# CRSC0002_MCU.net
KiCad netlist of a schematic drawn in Altium Designer
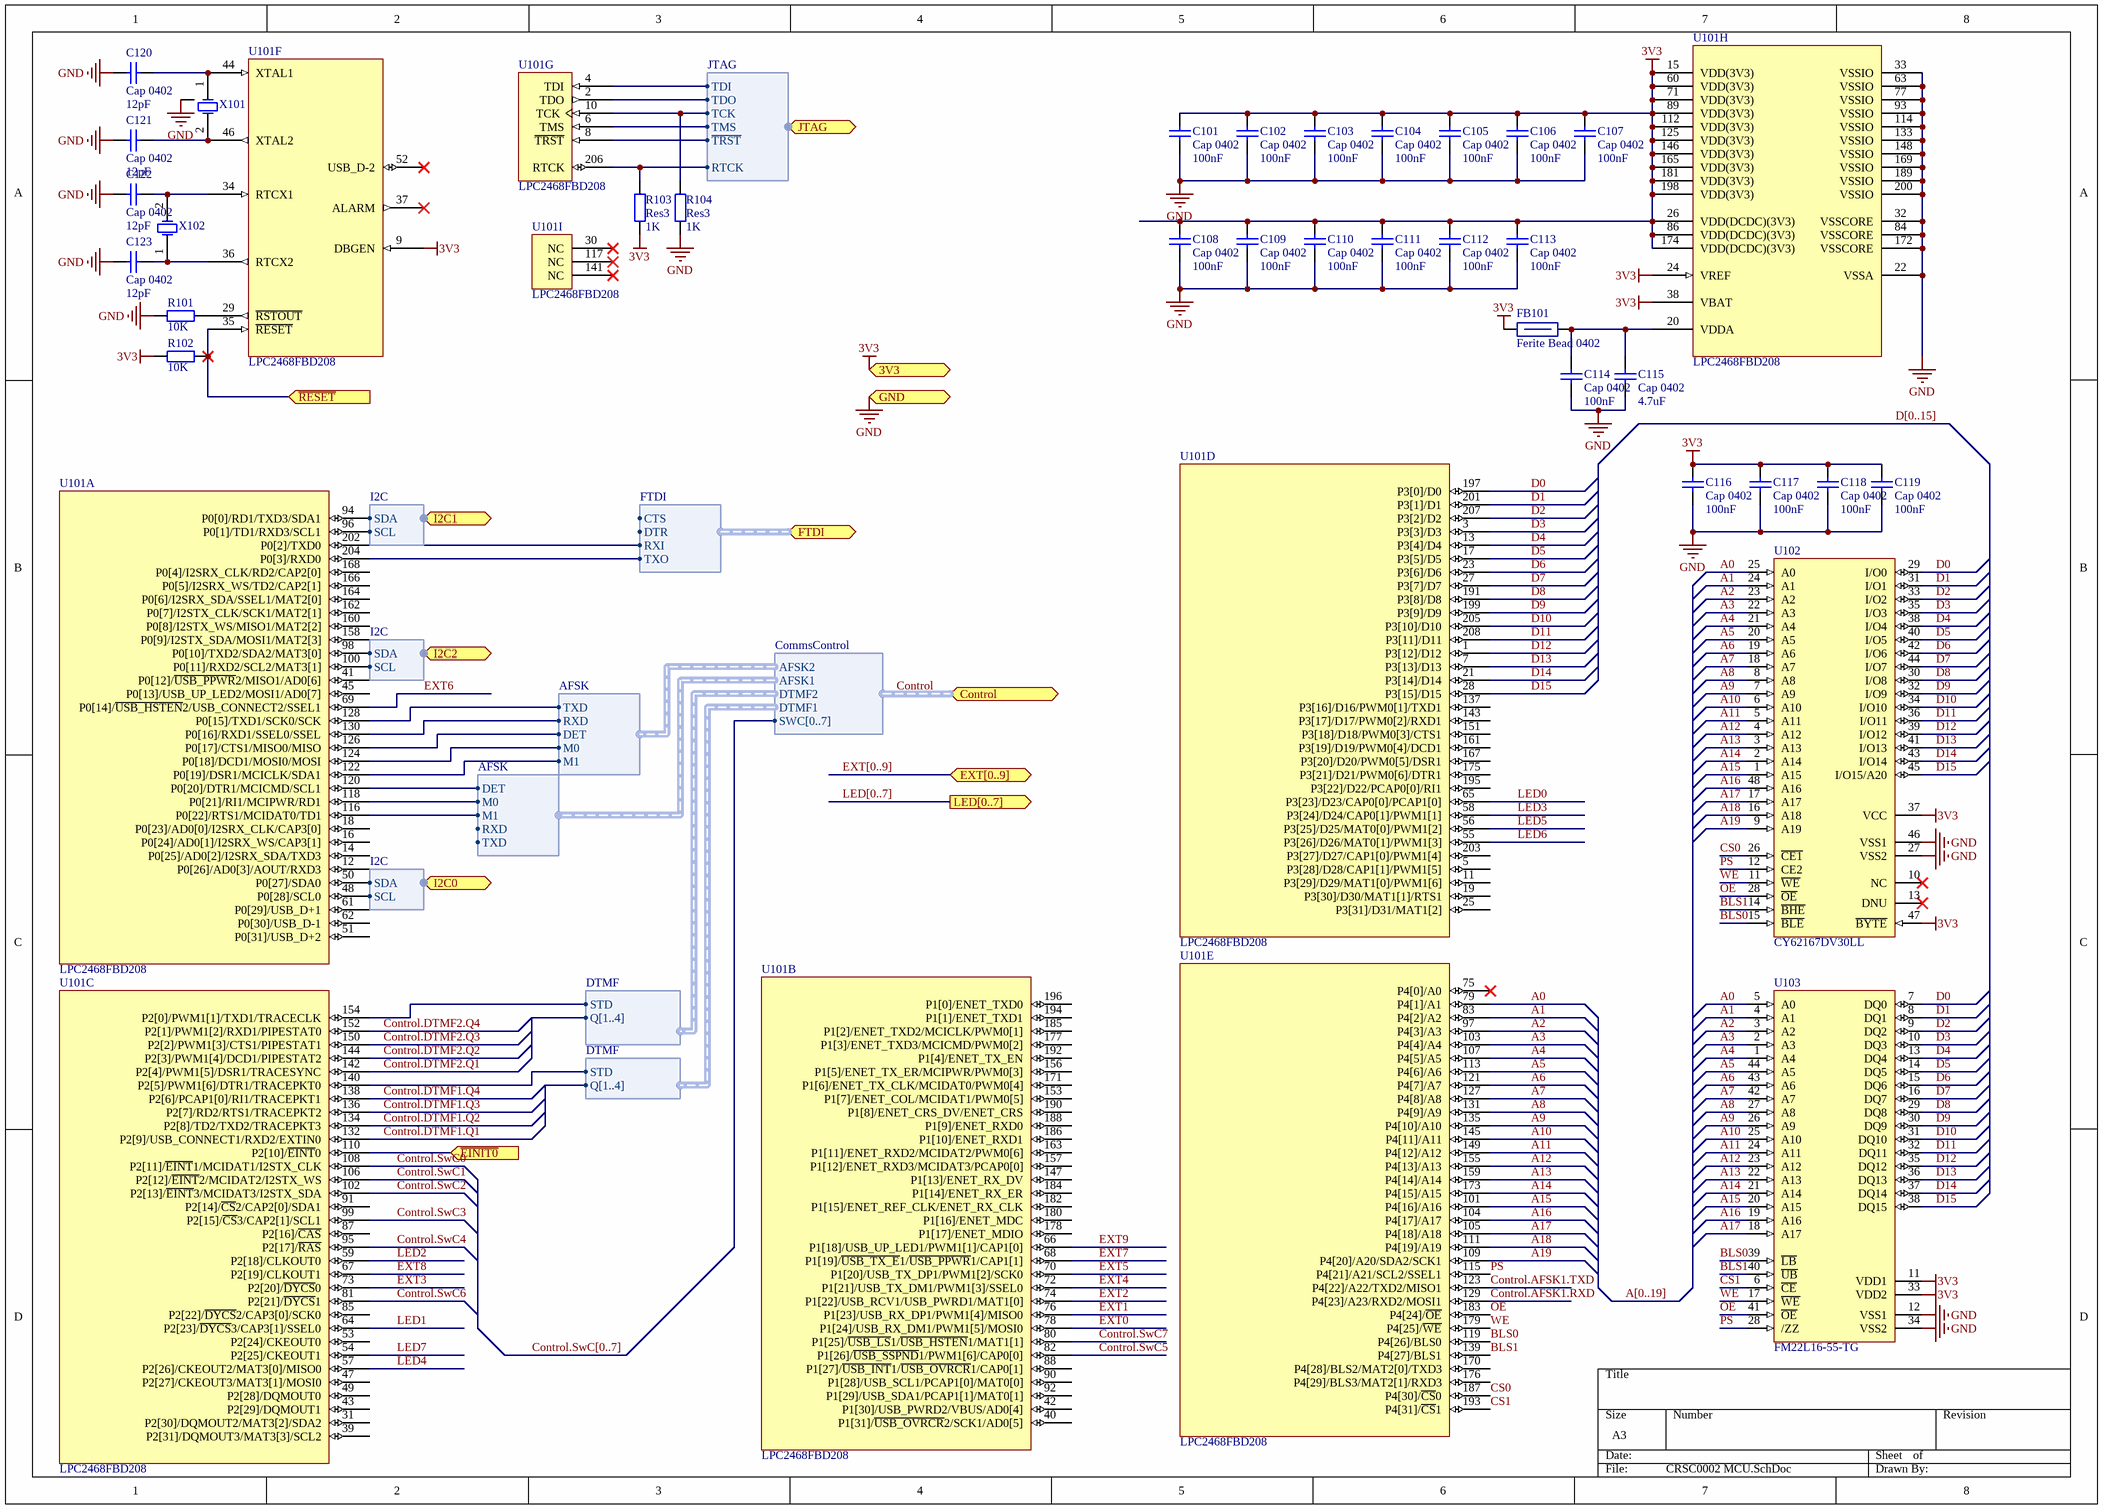
[diagram p0: CRSC0002 MCU.SchDoc]

(export (version "E")
  (design (tool "Eeschema 10.0.6"))
  (components
    (comp (ref "C101")
      (value "Cap 0402")
      (footprint "CAPC1005X06L")
      (description "Capacitor")
      (fields (field (name "ALTIUM_VALUE") "100nF") (field (name "PUBLISHER") "Altium Limited"))
      (libsource (lib "CSC") (part "Cap 0402"))
    )
    (comp (ref "C102")
      (value "Cap 0402")
      (footprint "CAPC1005X06L")
      (description "Capacitor")
      (fields (field (name "ALTIUM_VALUE") "100nF") (field (name "PUBLISHER") "Altium Limited"))
      (libsource (lib "CSC") (part "Cap 0402"))
    )
    (comp (ref "C103")
      (value "Cap 0402")
      (footprint "CAPC1005X06L")
      (description "Capacitor")
      (fields (field (name "ALTIUM_VALUE") "100nF") (field (name "PUBLISHER") "Altium Limited"))
      (libsource (lib "CSC") (part "Cap 0402"))
    )
    (comp (ref "C104")
      (value "Cap 0402")
      (footprint "CAPC1005X06L")
      (description "Capacitor")
      (fields (field (name "ALTIUM_VALUE") "100nF") (field (name "PUBLISHER") "Altium Limited"))
      (libsource (lib "CSC") (part "Cap 0402"))
    )
    (comp (ref "C105")
      (value "Cap 0402")
      (footprint "CAPC1005X06L")
      (description "Capacitor")
      (fields (field (name "ALTIUM_VALUE") "100nF") (field (name "PUBLISHER") "Altium Limited"))
      (libsource (lib "CSC") (part "Cap 0402"))
    )
    (comp (ref "C106")
      (value "Cap 0402")
      (footprint "CAPC1005X06L")
      (description "Capacitor")
      (fields (field (name "ALTIUM_VALUE") "100nF") (field (name "PUBLISHER") "Altium Limited"))
      (libsource (lib "CSC") (part "Cap 0402"))
    )
    (comp (ref "C107")
      (value "Cap 0402")
      (footprint "CAPC1005X06L")
      (description "Capacitor")
      (fields (field (name "ALTIUM_VALUE") "100nF") (field (name "PUBLISHER") "Altium Limited"))
      (libsource (lib "CSC") (part "Cap 0402"))
    )
    (comp (ref "C108")
      (value "Cap 0402")
      (footprint "CAPC1005X06L")
      (description "Capacitor")
      (fields (field (name "ALTIUM_VALUE") "100nF") (field (name "PUBLISHER") "Altium Limited"))
      (libsource (lib "CSC") (part "Cap 0402"))
    )
    (comp (ref "C109")
      (value "Cap 0402")
      (footprint "CAPC1005X06L")
      (description "Capacitor")
      (fields (field (name "ALTIUM_VALUE") "100nF") (field (name "PUBLISHER") "Altium Limited"))
      (libsource (lib "CSC") (part "Cap 0402"))
    )
    (comp (ref "C110")
      (value "Cap 0402")
      (footprint "CAPC1005X06L")
      (description "Capacitor")
      (fields (field (name "ALTIUM_VALUE") "100nF") (field (name "PUBLISHER") "Altium Limited"))
      (libsource (lib "CSC") (part "Cap 0402"))
    )
    (comp (ref "C111")
      (value "Cap 0402")
      (footprint "CAPC1005X06L")
      (description "Capacitor")
      (fields (field (name "ALTIUM_VALUE") "100nF") (field (name "PUBLISHER") "Altium Limited"))
      (libsource (lib "CSC") (part "Cap 0402"))
    )
    (comp (ref "C112")
      (value "Cap 0402")
      (footprint "CAPC1005X06L")
      (description "Capacitor")
      (fields (field (name "ALTIUM_VALUE") "100nF") (field (name "PUBLISHER") "Altium Limited"))
      (libsource (lib "CSC") (part "Cap 0402"))
    )
    (comp (ref "C113")
      (value "Cap 0402")
      (footprint "CAPC1005X06L")
      (description "Capacitor")
      (fields (field (name "ALTIUM_VALUE") "100nF") (field (name "PUBLISHER") "Altium Limited"))
      (libsource (lib "CSC") (part "Cap 0402"))
    )
    (comp (ref "C114")
      (value "Cap 0402")
      (footprint "CAPC1005X06L")
      (description "Capacitor")
      (fields (field (name "ALTIUM_VALUE") "100nF") (field (name "PUBLISHER") "Altium Limited"))
      (libsource (lib "CSC") (part "Cap 0402"))
    )
    (comp (ref "C115")
      (value "Cap 0402")
      (footprint "CAPC1005X06L")
      (description "Capacitor")
      (fields (field (name "ALTIUM_VALUE") "4.7uF") (field (name "PUBLISHER") "Altium Limited"))
      (libsource (lib "CSC") (part "Cap 0402"))
    )
    (comp (ref "C116")
      (value "Cap 0402")
      (footprint "CAPC1005X06L")
      (description "Capacitor")
      (fields (field (name "ALTIUM_VALUE") "100nF") (field (name "PUBLISHER") "Altium Limited"))
      (libsource (lib "CSC") (part "Cap 0402"))
    )
    (comp (ref "C117")
      (value "Cap 0402")
      (footprint "CAPC1005X06L")
      (description "Capacitor")
      (fields (field (name "ALTIUM_VALUE") "100nF") (field (name "PUBLISHER") "Altium Limited"))
      (libsource (lib "CSC") (part "Cap 0402"))
    )
    (comp (ref "C118")
      (value "Cap 0402")
      (footprint "CAPC1005X06L")
      (description "Capacitor")
      (fields (field (name "ALTIUM_VALUE") "100nF") (field (name "PUBLISHER") "Altium Limited"))
      (libsource (lib "CSC") (part "Cap 0402"))
    )
    (comp (ref "C119")
      (value "Cap 0402")
      (footprint "CAPC1005X06L")
      (description "Capacitor")
      (fields (field (name "ALTIUM_VALUE") "100nF") (field (name "PUBLISHER") "Altium Limited"))
      (libsource (lib "CSC") (part "Cap 0402"))
    )
    (comp (ref "C120")
      (value "Cap 0402")
      (footprint "CAPC1005X06L")
      (description "Capacitor")
      (fields (field (name "ALTIUM_VALUE") "12pF") (field (name "PUBLISHER") "Altium Limited"))
      (libsource (lib "CSC") (part "Cap 0402"))
    )
    (comp (ref "C121")
      (value "Cap 0402")
      (footprint "CAPC1005X06L")
      (description "Capacitor")
      (fields (field (name "ALTIUM_VALUE") "12pF") (field (name "PUBLISHER") "Altium Limited"))
      (libsource (lib "CSC") (part "Cap 0402"))
    )
    (comp (ref "C122")
      (value "Cap 0402")
      (footprint "CAPC1005X06L")
      (description "Capacitor")
      (fields (field (name "ALTIUM_VALUE") "12pF") (field (name "PUBLISHER") "Altium Limited"))
      (libsource (lib "CSC") (part "Cap 0402"))
    )
    (comp (ref "C123")
      (value "Cap 0402")
      (footprint "CAPC1005X06L")
      (description "Capacitor")
      (fields (field (name "ALTIUM_VALUE") "12pF") (field (name "PUBLISHER") "Altium Limited"))
      (libsource (lib "CSC") (part "Cap 0402"))
    )
    (comp (ref "FB101")
      (value "Ferite Bead 0402")
      (footprint "INDC1005X06L")
      (description "Ferite Bead : 0402")
      (fields (field (name "PUBLISHER") "Altium Limited"))
      (libsource (lib "CSC") (part "FB_0402"))
    )
    (comp (ref "R101")
      (value "10K")
      (footprint "RESC1005X06L")
      (description "Resistor")
      (fields (field (name "Comment") "Res3") (field (name "PUBLISHER") "Altium Limited"))
      (libsource (lib "") (part "Res3_1"))
    )
    (comp (ref "R102")
      (value "10K")
      (footprint "RESC1005X06L")
      (description "Resistor")
      (fields (field (name "Comment") "Res3") (field (name "PUBLISHER") "Altium Limited"))
      (libsource (lib "") (part "Res3_1"))
    )
    (comp (ref "R103")
      (value "Res3")
      (footprint "RESC1005X06L")
      (description "Resistor")
      (fields (field (name "ALTIUM_VALUE") "1K") (field (name "PUBLISHER") "Altium Limited"))
      (libsource (lib "CSC") (part "Res3"))
    )
    (comp (ref "R104")
      (value "Res3")
      (footprint "RESC1005X06L")
      (description "Resistor")
      (fields (field (name "ALTIUM_VALUE") "1K") (field (name "PUBLISHER") "Altium Limited"))
      (libsource (lib "CSC") (part "Res3"))
    )
    (comp (ref "U101")
      (value "LPC2468FBD208")
      (footprint "TSQFP50P3000X3000X160-208L")
      (description "ARM7 16/32-Bit Microcontroller, 512KB Flash, 98KB RAM, 208-Lead LQFP")
      (fields (field (name "PUBLISHER") "Altium Limited"))
      (libsource (lib "") (part "LPC2468FBD208_1"))
    )
    (comp (ref "U102")
      (value "CY62167DV30LL")
      (footprint "TSSOP50P2000X120-48L")
      (description "16-Mbit (1M x 16) Static RAM")
      (fields (field (name "PUBLISHER") "Altium Limited"))
      (libsource (lib "CSC") (part "CY62167DV30LL"))
    )
    (comp (ref "U103")
      (value "FM22L16-55-TG")
      (footprint "TSOP80P1180X120-44L")
      (description "FRAM, 2MB, 3V, 60NS, 44TSOP2")
      (libsource (lib "CSC") (part "FM22L16-55-TG"))
    )
    (comp (ref "X101")
      (value "Crystal Oscilator")
      (footprint "7M")
      (description "Crystal Oscillator")
      (fields (field (name "PUBLISHER") "Altium Limited"))
      (libsource (lib "CSC") (part "C.O. 4pins"))
    )
    (comp (ref "X102")
      (value "Crystal Oscilator")
      (footprint "9H T10")
      (description "Crystal Oscillator")
      (fields (field (name "PUBLISHER") "Altium Limited"))
      (libsource (lib "CSC") (part "C.O. 2pins"))
    )
  )
  (nets
    (net (code "7") (name "/A0") (class "Default")
      (node (ref "U101") (pin "79") (pinfunction "P4[1]/A1_79") (pintype "bidirectional"))
      (node (ref "U102") (pin "25") (pinfunction "A0_25") (pintype "input"))
      (node (ref "U103") (pin "5") (pinfunction "A0_5") (pintype "input"))
    )
    (net (code "8") (name "/A1") (class "Default")
      (node (ref "U101") (pin "83") (pinfunction "P4[2]/A2_83") (pintype "bidirectional"))
      (node (ref "U102") (pin "24") (pinfunction "A1_24") (pintype "input"))
      (node (ref "U103") (pin "4") (pinfunction "A1_4") (pintype "input"))
    )
    (net (code "9") (name "/A2") (class "Default")
      (node (ref "U101") (pin "97") (pinfunction "P4[3]/A3_97") (pintype "bidirectional"))
      (node (ref "U102") (pin "23") (pinfunction "A2_23") (pintype "input"))
      (node (ref "U103") (pin "3") (pinfunction "A2_3") (pintype "input"))
    )
    (net (code "10") (name "/A3") (class "Default")
      (node (ref "U101") (pin "103") (pinfunction "P4[4]/A4_103") (pintype "bidirectional"))
      (node (ref "U102") (pin "22") (pinfunction "A3_22") (pintype "input"))
      (node (ref "U103") (pin "2") (pinfunction "A3_2") (pintype "input"))
    )
    (net (code "11") (name "/A4") (class "Default")
      (node (ref "U101") (pin "107") (pinfunction "P4[5]/A5_107") (pintype "bidirectional"))
      (node (ref "U102") (pin "21") (pinfunction "A4_21") (pintype "input"))
      (node (ref "U103") (pin "1") (pinfunction "A4_1") (pintype "input"))
    )
    (net (code "12") (name "/A5") (class "Default")
      (node (ref "U101") (pin "113") (pinfunction "P4[6]/A6_113") (pintype "bidirectional"))
      (node (ref "U102") (pin "20") (pinfunction "A5_20") (pintype "input"))
      (node (ref "U103") (pin "44") (pinfunction "A5_44") (pintype "input"))
    )
    (net (code "13") (name "/A6") (class "Default")
      (node (ref "U101") (pin "121") (pinfunction "P4[7]/A7_121") (pintype "bidirectional"))
      (node (ref "U102") (pin "19") (pinfunction "A6_19") (pintype "input"))
      (node (ref "U103") (pin "43") (pinfunction "A6_43") (pintype "input"))
    )
    (net (code "14") (name "/A7") (class "Default")
      (node (ref "U101") (pin "127") (pinfunction "P4[8]/A8_127") (pintype "bidirectional"))
      (node (ref "U102") (pin "18") (pinfunction "A7_18") (pintype "input"))
      (node (ref "U103") (pin "42") (pinfunction "A7_42") (pintype "input"))
    )
    (net (code "15") (name "/A8") (class "Default")
      (node (ref "U101") (pin "131") (pinfunction "P4[9]/A9_131") (pintype "bidirectional"))
      (node (ref "U102") (pin "8") (pinfunction "A8_8") (pintype "input"))
      (node (ref "U103") (pin "27") (pinfunction "A8_27") (pintype "input"))
    )
    (net (code "16") (name "/A9") (class "Default")
      (node (ref "U101") (pin "135") (pinfunction "P4[10]/A10_135") (pintype "bidirectional"))
      (node (ref "U102") (pin "7") (pinfunction "A9_7") (pintype "input"))
      (node (ref "U103") (pin "26") (pinfunction "A9_26") (pintype "input"))
    )
    (net (code "17") (name "/A10") (class "Default")
      (node (ref "U101") (pin "145") (pinfunction "P4[11]/A11_145") (pintype "bidirectional"))
      (node (ref "U102") (pin "6") (pinfunction "A10_6") (pintype "input"))
      (node (ref "U103") (pin "25") (pinfunction "A10_25") (pintype "input"))
    )
    (net (code "18") (name "/A11") (class "Default")
      (node (ref "U101") (pin "149") (pinfunction "P4[12]/A12_149") (pintype "bidirectional"))
      (node (ref "U102") (pin "5") (pinfunction "A11_5") (pintype "input"))
      (node (ref "U103") (pin "24") (pinfunction "A11_24") (pintype "input"))
    )
    (net (code "19") (name "/A12") (class "Default")
      (node (ref "U101") (pin "155") (pinfunction "P4[13]/A13_155") (pintype "bidirectional"))
      (node (ref "U102") (pin "4") (pinfunction "A12_4") (pintype "input"))
      (node (ref "U103") (pin "23") (pinfunction "A12_23") (pintype "input"))
    )
    (net (code "20") (name "/A13") (class "Default")
      (node (ref "U101") (pin "159") (pinfunction "P4[14]/A14_159") (pintype "bidirectional"))
      (node (ref "U102") (pin "3") (pinfunction "A13_3") (pintype "input"))
      (node (ref "U103") (pin "22") (pinfunction "A13_22") (pintype "input"))
    )
    (net (code "21") (name "/A14") (class "Default")
      (node (ref "U101") (pin "173") (pinfunction "P4[15]/A15_173") (pintype "bidirectional"))
      (node (ref "U102") (pin "2") (pinfunction "A14_2") (pintype "input"))
      (node (ref "U103") (pin "21") (pinfunction "A14_21") (pintype "input"))
    )
    (net (code "22") (name "/A15") (class "Default")
      (node (ref "U101") (pin "101") (pinfunction "P4[16]/A16_101") (pintype "bidirectional"))
      (node (ref "U102") (pin "1") (pinfunction "A15_1") (pintype "input"))
      (node (ref "U103") (pin "20") (pinfunction "A15_20") (pintype "input"))
    )
    (net (code "23") (name "/A16") (class "Default")
      (node (ref "U101") (pin "104") (pinfunction "P4[17]/A17_104") (pintype "bidirectional"))
      (node (ref "U102") (pin "48") (pinfunction "A16_48") (pintype "input"))
      (node (ref "U103") (pin "19") (pinfunction "A16_19") (pintype "input"))
    )
    (net (code "24") (name "/A17") (class "Default")
      (node (ref "U101") (pin "105") (pinfunction "P4[18]/A18_105") (pintype "bidirectional"))
      (node (ref "U102") (pin "17") (pinfunction "A17_17") (pintype "input"))
      (node (ref "U103") (pin "18") (pinfunction "A17_18") (pintype "input"))
    )
    (net (code "25") (name "/A18") (class "Default")
      (node (ref "U101") (pin "111") (pinfunction "P4[19]/A19_111") (pintype "bidirectional"))
      (node (ref "U102") (pin "16") (pinfunction "A18_16") (pintype "input"))
    )
    (net (code "26") (name "/A19") (class "Default")
      (node (ref "U101") (pin "109") (pinfunction "P4[20]/A20/SDA2/SCK1_109") (pintype "bidirectional"))
      (node (ref "U102") (pin "9") (pinfunction "A19_9") (pintype "input"))
    )
    (net (code "28") (name "/BLS0") (class "Default")
      (node (ref "U101") (pin "119") (pinfunction "P4[26]/BLS0_119") (pintype "bidirectional"))
      (node (ref "U102") (pin "15") (pinfunction "~{BLE}_15") (pintype "input"))
      (node (ref "U103") (pin "39") (pinfunction "~{LB}_39") (pintype "input"))
    )
    (net (code "29") (name "/BLS1") (class "Default")
      (node (ref "U101") (pin "139") (pinfunction "P4[27]/BLS1_139") (pintype "bidirectional"))
      (node (ref "U102") (pin "14") (pinfunction "~{BHE}_14") (pintype "input"))
      (node (ref "U103") (pin "40") (pinfunction "~{UB}_40") (pintype "input"))
    )
    (net (code "30") (name "/CS0") (class "Default")
      (node (ref "U101") (pin "187") (pinfunction "P4[30]/~{CS}0_187") (pintype "bidirectional"))
      (node (ref "U102") (pin "26") (pinfunction "~{CE1}_26") (pintype "input"))
    )
    (net (code "31") (name "/CS1") (class "Default")
      (node (ref "U101") (pin "193") (pinfunction "P4[31]/~{CS}1_193") (pintype "bidirectional"))
      (node (ref "U103") (pin "6") (pinfunction "~{CE}_6") (pintype "input"))
    )
    (net (code "32") (name "/Control.AFSK1.RXD") (class "Default")
      (node (ref "U101") (pin "129") (pinfunction "P4[23]/A23/RXD2/MOSI1_129") (pintype "bidirectional"))
    )
    (net (code "33") (name "/Control.AFSK1.TXD") (class "Default")
      (node (ref "U101") (pin "123") (pinfunction "P4[22]/A22/TXD2/MISO1_123") (pintype "bidirectional"))
    )
    (net (code "34") (name "/Control.DTMF1.Q1") (class "Default")
      (node (ref "U101") (pin "132") (pinfunction "P2[9]/USB_CONNECT1/RXD2/EXTIN0_132") (pintype "bidirectional"))
    )
    (net (code "35") (name "/Control.DTMF1.Q2") (class "Default")
      (node (ref "U101") (pin "134") (pinfunction "P2[8]/TD2/TXD2/TRACEPKT3_134") (pintype "bidirectional"))
    )
    (net (code "36") (name "/Control.DTMF1.Q3") (class "Default")
      (node (ref "U101") (pin "136") (pinfunction "P2[7]/RD2/RTS1/TRACEPKT2_136") (pintype "bidirectional"))
    )
    (net (code "37") (name "/Control.DTMF1.Q4") (class "Default")
      (node (ref "U101") (pin "138") (pinfunction "P2[6]/PCAP1[0]/RI1/TRACEPKT1_138") (pintype "bidirectional"))
    )
    (net (code "38") (name "/Control.DTMF2.Q1") (class "Default")
      (node (ref "U101") (pin "142") (pinfunction "P2[4]/PWM1[5]/DSR1/TRACESYNC_142") (pintype "bidirectional"))
    )
    (net (code "39") (name "/Control.DTMF2.Q2") (class "Default")
      (node (ref "U101") (pin "144") (pinfunction "P2[3]/PWM1[4]/DCD1/PIPESTAT2_144") (pintype "bidirectional"))
    )
    (net (code "40") (name "/Control.DTMF2.Q3") (class "Default")
      (node (ref "U101") (pin "150") (pinfunction "P2[2]/PWM1[3]/CTS1/PIPESTAT1_150") (pintype "bidirectional"))
    )
    (net (code "41") (name "/Control.DTMF2.Q4") (class "Default")
      (node (ref "U101") (pin "152") (pinfunction "P2[1]/PWM1[2]/RXD1/PIPESTAT0_152") (pintype "bidirectional"))
    )
    (net (code "42") (name "/Control.SwC0") (class "Default")
      (node (ref "U101") (pin "108") (pinfunction "P2[11]/~{EINT}1/MCIDAT1/I2STX_CLK_108") (pintype "bidirectional"))
    )
    (net (code "43") (name "/Control.SwC1") (class "Default")
      (node (ref "U101") (pin "106") (pinfunction "P2[12]/~{EINT}2/MCIDAT2/I2STX_WS_106") (pintype "bidirectional"))
    )
    (net (code "44") (name "/Control.SwC2") (class "Default")
      (node (ref "U101") (pin "102") (pinfunction "P2[13]/~{EINT}3/MCIDAT3/I2STX_SDA_102") (pintype "bidirectional"))
    )
    (net (code "45") (name "/Control.SwC3") (class "Default")
      (node (ref "U101") (pin "99") (pinfunction "P2[15]/~{CS}3/CAP2[1]/SCL1_99") (pintype "bidirectional"))
    )
    (net (code "46") (name "/Control.SwC4") (class "Default")
      (node (ref "U101") (pin "95") (pinfunction "P2[17]/~{RAS}_95") (pintype "bidirectional"))
    )
    (net (code "47") (name "/Control.SwC5") (class "Default")
      (node (ref "U101") (pin "82") (pinfunction "P1[26]/~{USB_SSPND}1/PWM1[6]/CAP0[0]_82") (pintype "bidirectional"))
    )
    (net (code "48") (name "/Control.SwC6") (class "Default")
      (node (ref "U101") (pin "81") (pinfunction "P2[21]/~{DYCS}1_81") (pintype "bidirectional"))
    )
    (net (code "49") (name "/Control.SwC7") (class "Default")
      (node (ref "U101") (pin "80") (pinfunction "P1[25]/~{USB_LS}1/~{USB_HSTEN}1/MAT1[1]_80") (pintype "bidirectional"))
    )
    (net (code "50") (name "/D0") (class "Default")
      (node (ref "U101") (pin "197") (pinfunction "P3[0]/D0_197") (pintype "bidirectional"))
      (node (ref "U102") (pin "29") (pinfunction "I/O0_29") (pintype "bidirectional"))
      (node (ref "U103") (pin "7") (pinfunction "DQ0_7") (pintype "bidirectional"))
    )
    (net (code "51") (name "/D1") (class "Default")
      (node (ref "U101") (pin "201") (pinfunction "P3[1]/D1_201") (pintype "bidirectional"))
      (node (ref "U102") (pin "31") (pinfunction "I/O1_31") (pintype "bidirectional"))
      (node (ref "U103") (pin "8") (pinfunction "DQ1_8") (pintype "bidirectional"))
    )
    (net (code "52") (name "/D2") (class "Default")
      (node (ref "U101") (pin "207") (pinfunction "P3[2]/D2_207") (pintype "bidirectional"))
      (node (ref "U102") (pin "33") (pinfunction "I/O2_33") (pintype "bidirectional"))
      (node (ref "U103") (pin "9") (pinfunction "DQ2_9") (pintype "bidirectional"))
    )
    (net (code "53") (name "/D3") (class "Default")
      (node (ref "U101") (pin "3") (pinfunction "P3[3]/D3_3") (pintype "bidirectional"))
      (node (ref "U102") (pin "35") (pinfunction "I/O3_35") (pintype "bidirectional"))
      (node (ref "U103") (pin "10") (pinfunction "DQ3_10") (pintype "bidirectional"))
    )
    (net (code "54") (name "/D4") (class "Default")
      (node (ref "U101") (pin "13") (pinfunction "P3[4]/D4_13") (pintype "bidirectional"))
      (node (ref "U102") (pin "38") (pinfunction "I/O4_38") (pintype "bidirectional"))
      (node (ref "U103") (pin "13") (pinfunction "DQ4_13") (pintype "bidirectional"))
    )
    (net (code "55") (name "/D5") (class "Default")
      (node (ref "U101") (pin "17") (pinfunction "P3[5]/D5_17") (pintype "bidirectional"))
      (node (ref "U102") (pin "40") (pinfunction "I/O5_40") (pintype "bidirectional"))
      (node (ref "U103") (pin "14") (pinfunction "DQ5_14") (pintype "bidirectional"))
    )
    (net (code "56") (name "/D6") (class "Default")
      (node (ref "U101") (pin "23") (pinfunction "P3[6]/D6_23") (pintype "bidirectional"))
      (node (ref "U102") (pin "42") (pinfunction "I/O6_42") (pintype "bidirectional"))
      (node (ref "U103") (pin "15") (pinfunction "DQ6_15") (pintype "bidirectional"))
    )
    (net (code "57") (name "/D7") (class "Default")
      (node (ref "U101") (pin "27") (pinfunction "P3[7]/D7_27") (pintype "bidirectional"))
      (node (ref "U102") (pin "44") (pinfunction "I/O7_44") (pintype "bidirectional"))
      (node (ref "U103") (pin "16") (pinfunction "DQ7_16") (pintype "bidirectional"))
    )
    (net (code "58") (name "/D8") (class "Default")
      (node (ref "U101") (pin "191") (pinfunction "P3[8]/D8_191") (pintype "bidirectional"))
      (node (ref "U102") (pin "30") (pinfunction "I/O8_30") (pintype "bidirectional"))
      (node (ref "U103") (pin "29") (pinfunction "DQ8_29") (pintype "bidirectional"))
    )
    (net (code "59") (name "/D9") (class "Default")
      (node (ref "U101") (pin "199") (pinfunction "P3[9]/D9_199") (pintype "bidirectional"))
      (node (ref "U102") (pin "32") (pinfunction "I/O9_32") (pintype "bidirectional"))
      (node (ref "U103") (pin "30") (pinfunction "DQ9_30") (pintype "bidirectional"))
    )
    (net (code "60") (name "/D10") (class "Default")
      (node (ref "U101") (pin "205") (pinfunction "P3[10]/D10_205") (pintype "bidirectional"))
      (node (ref "U102") (pin "34") (pinfunction "I/O10_34") (pintype "bidirectional"))
      (node (ref "U103") (pin "31") (pinfunction "DQ10_31") (pintype "bidirectional"))
    )
    (net (code "61") (name "/D11") (class "Default")
      (node (ref "U101") (pin "208") (pinfunction "P3[11]/D11_208") (pintype "bidirectional"))
      (node (ref "U102") (pin "36") (pinfunction "I/O11_36") (pintype "bidirectional"))
      (node (ref "U103") (pin "32") (pinfunction "DQ11_32") (pintype "bidirectional"))
    )
    (net (code "62") (name "/D12") (class "Default")
      (node (ref "U101") (pin "1") (pinfunction "P3[12]/D12_1") (pintype "bidirectional"))
      (node (ref "U102") (pin "39") (pinfunction "I/O12_39") (pintype "bidirectional"))
      (node (ref "U103") (pin "35") (pinfunction "DQ12_35") (pintype "bidirectional"))
    )
    (net (code "63") (name "/D13") (class "Default")
      (node (ref "U101") (pin "7") (pinfunction "P3[13]/D13_7") (pintype "bidirectional"))
      (node (ref "U102") (pin "41") (pinfunction "I/O13_41") (pintype "bidirectional"))
      (node (ref "U103") (pin "36") (pinfunction "DQ13_36") (pintype "bidirectional"))
    )
    (net (code "64") (name "/D14") (class "Default")
      (node (ref "U101") (pin "21") (pinfunction "P3[14]/D14_21") (pintype "bidirectional"))
      (node (ref "U102") (pin "43") (pinfunction "I/O14_43") (pintype "bidirectional"))
      (node (ref "U103") (pin "37") (pinfunction "DQ14_37") (pintype "bidirectional"))
    )
    (net (code "65") (name "/D15") (class "Default")
      (node (ref "U101") (pin "28") (pinfunction "P3[15]/D15_28") (pintype "bidirectional"))
      (node (ref "U102") (pin "45") (pinfunction "I/O15/A20_45") (pintype "bidirectional"))
      (node (ref "U103") (pin "38") (pinfunction "DQ15_38") (pintype "bidirectional"))
    )
    (net (code "68") (name "/EXT0") (class "Default")
      (node (ref "U101") (pin "78") (pinfunction "P1[24]/USB_RX_DM1/PWM1[5]/MOSI0_78") (pintype "bidirectional"))
    )
    (net (code "69") (name "/EXT1") (class "Default")
      (node (ref "U101") (pin "76") (pinfunction "P1[23]/USB_RX_DP1/PWM1[4]/MISO0_76") (pintype "bidirectional"))
    )
    (net (code "70") (name "/EXT2") (class "Default")
      (node (ref "U101") (pin "74") (pinfunction "P1[22]/USB_RCV1/USB_PWRD1/MAT1[0]_74") (pintype "bidirectional"))
    )
    (net (code "71") (name "/EXT3") (class "Default")
      (node (ref "U101") (pin "73") (pinfunction "P2[20]/~{DYCS}0_73") (pintype "bidirectional"))
    )
    (net (code "72") (name "/EXT4") (class "Default")
      (node (ref "U101") (pin "72") (pinfunction "P1[21]/USB_TX_DM1/PWM1[3]/SSEL0_72") (pintype "bidirectional"))
    )
    (net (code "73") (name "/EXT5") (class "Default")
      (node (ref "U101") (pin "70") (pinfunction "P1[20]/USB_TX_DP1/PWM1[2]/SCK0_70") (pintype "bidirectional"))
    )
    (net (code "74") (name "/EXT6") (class "Default")
      (node (ref "U101") (pin "69") (pinfunction "P0[14]/~{USB_HSTEN}2/USB_CONNECT2/SSEL1_69") (pintype "bidirectional"))
    )
    (net (code "75") (name "/EXT7") (class "Default")
      (node (ref "U101") (pin "68") (pinfunction "P1[19]/~{USB_TX_E}1/~{USB_PPWR}1/CAP1[1]_68") (pintype "bidirectional"))
    )
    (net (code "76") (name "/EXT8") (class "Default")
      (node (ref "U101") (pin "67") (pinfunction "P2[19]/CLKOUT1_67") (pintype "bidirectional"))
    )
    (net (code "77") (name "/EXT9") (class "Default")
      (node (ref "U101") (pin "66") (pinfunction "P1[18]/USB_UP_LED1/PWM1[1]/CAP1[0]_66") (pintype "bidirectional"))
    )
    (net (code "79") (name "/LED0") (class "Default")
      (node (ref "U101") (pin "65") (pinfunction "P3[23]/D23/CAP0[0]/PCAP1[0]_65") (pintype "bidirectional"))
    )
    (net (code "80") (name "/LED1") (class "Default")
      (node (ref "U101") (pin "64") (pinfunction "P2[23]/~{DYCS}3/CAP3[1]/SSEL0_64") (pintype "bidirectional"))
    )
    (net (code "81") (name "/LED2") (class "Default")
      (node (ref "U101") (pin "59") (pinfunction "P2[18]/CLKOUT0_59") (pintype "bidirectional"))
    )
    (net (code "82") (name "/LED3") (class "Default")
      (node (ref "U101") (pin "58") (pinfunction "P3[24]/D24/CAP0[1]/PWM1[1]_58") (pintype "bidirectional"))
    )
    (net (code "83") (name "/LED4") (class "Default")
      (node (ref "U101") (pin "57") (pinfunction "P2[26]/CKEOUT2/MAT3[0]/MISO0_57") (pintype "bidirectional"))
    )
    (net (code "84") (name "/LED5") (class "Default")
      (node (ref "U101") (pin "56") (pinfunction "P3[25]/D25/MAT0[0]/PWM1[2]_56") (pintype "bidirectional"))
    )
    (net (code "85") (name "/LED6") (class "Default")
      (node (ref "U101") (pin "55") (pinfunction "P3[26]/D26/MAT0[1]/PWM1[3]_55") (pintype "bidirectional"))
    )
    (net (code "86") (name "/LED7") (class "Default")
      (node (ref "U101") (pin "54") (pinfunction "P2[25]/CKEOUT1_54") (pintype "bidirectional"))
    )
    (net (code "88") (name "/OE") (class "Default")
      (node (ref "U101") (pin "183") (pinfunction "P4[24]/~{OE}_183") (pintype "bidirectional"))
      (node (ref "U102") (pin "28") (pinfunction "~{OE}_28") (pintype "input"))
      (node (ref "U103") (pin "41") (pinfunction "~{OE}_41") (pintype "input"))
    )
    (net (code "89") (name "/PS") (class "Default")
      (node (ref "U101") (pin "115") (pinfunction "P4[21]/A21/SCL2/SSEL1_115") (pintype "bidirectional"))
      (node (ref "U102") (pin "12") (pinfunction "CE2_12") (pintype "input"))
      (node (ref "U103") (pin "28") (pinfunction "/ZZ_28") (pintype "input"))
    )
    (net (code "90") (name "/RTCK") (class "Default")
      (node (ref "R103") (pin "1") (pinfunction "1_1") (pintype "passive"))
      (node (ref "U101") (pin "206") (pinfunction "RTCK_206") (pintype "bidirectional"))
    )
    (net (code "91") (name "/RXI") (class "Default")
      (node (ref "U101") (pin "202") (pinfunction "P0[2]/TXD0_202") (pintype "bidirectional"))
    )
    (net (code "92") (name "/TCK") (class "Default")
      (node (ref "R104") (pin "1") (pinfunction "1_1") (pintype "passive"))
      (node (ref "U101") (pin "10") (pinfunction "TCK_10") (pintype "input"))
    )
    (net (code "93") (name "/TDI") (class "Default")
      (node (ref "U101") (pin "4") (pinfunction "TDI_4") (pintype "input"))
    )
    (net (code "94") (name "/TDO") (class "Default")
      (node (ref "U101") (pin "2") (pinfunction "TDO_2") (pintype "output"))
    )
    (net (code "95") (name "/TMS") (class "Default")
      (node (ref "U101") (pin "6") (pinfunction "TMS_6") (pintype "input"))
    )
    (net (code "96") (name "/TXO") (class "Default")
      (node (ref "U101") (pin "204") (pinfunction "P0[3]/RXD0_204") (pintype "bidirectional"))
    )
    (net (code "97") (name "/WE") (class "Default")
      (node (ref "U101") (pin "179") (pinfunction "P4[25]/~{WE}_179") (pintype "bidirectional"))
      (node (ref "U102") (pin "11") (pinfunction "~{WE}_11") (pintype "input"))
      (node (ref "U103") (pin "17") (pinfunction "~{WE}_17") (pintype "input"))
    )
    (net (code "104") (name "/~{EINIT0}") (class "Default")
      (node (ref "U101") (pin "110") (pinfunction "P2[10]/~{EINT}0_110") (pintype "bidirectional"))
    )
    (net (code "105") (name "/~{RESET}") (class "Default")
      (node (ref "R102") (pin "1") (pinfunction "1_1") (pintype "passive"))
      (node (ref "U101") (pin "35") (pinfunction "~{RESET}_35") (pintype "input"))
    )
    (net (code "106") (name "/~{TRST}") (class "Default")
      (node (ref "U101") (pin "8") (pinfunction "~{TRST}_8") (pintype "input"))
    )
    (net (code "107") (name "3V3") (class "Default")
      (node (ref "C101") (pin "2") (pinfunction "2_2") (pintype "passive"))
      (node (ref "C102") (pin "2") (pinfunction "2_2") (pintype "passive"))
      (node (ref "C103") (pin "2") (pinfunction "2_2") (pintype "passive"))
      (node (ref "C104") (pin "2") (pinfunction "2_2") (pintype "passive"))
      (node (ref "C105") (pin "2") (pinfunction "2_2") (pintype "passive"))
      (node (ref "C106") (pin "2") (pinfunction "2_2") (pintype "passive"))
      (node (ref "C107") (pin "2") (pinfunction "2_2") (pintype "passive"))
      (node (ref "C108") (pin "2") (pinfunction "2_2") (pintype "passive"))
      (node (ref "C109") (pin "2") (pinfunction "2_2") (pintype "passive"))
      (node (ref "C110") (pin "2") (pinfunction "2_2") (pintype "passive"))
      (node (ref "C111") (pin "2") (pinfunction "2_2") (pintype "passive"))
      (node (ref "C112") (pin "2") (pinfunction "2_2") (pintype "passive"))
      (node (ref "C113") (pin "2") (pinfunction "2_2") (pintype "passive"))
      (node (ref "C116") (pin "2") (pinfunction "2_2") (pintype "passive"))
      (node (ref "C117") (pin "2") (pinfunction "2_2") (pintype "passive"))
      (node (ref "C118") (pin "2") (pinfunction "2_2") (pintype "passive"))
      (node (ref "C119") (pin "2") (pinfunction "2_2") (pintype "passive"))
      (node (ref "FB101") (pin "1") (pinfunction "1_1") (pintype "passive"))
      (node (ref "R102") (pin "2") (pinfunction "2_2") (pintype "passive"))
      (node (ref "R103") (pin "2") (pinfunction "2_2") (pintype "passive"))
      (node (ref "U101") (pin "112") (pinfunction "VDD(3V3)_112") (pintype "power_in"))
      (node (ref "U101") (pin "125") (pinfunction "VDD(3V3)_125") (pintype "power_in"))
      (node (ref "U101") (pin "146") (pinfunction "VDD(3V3)_146") (pintype "power_in"))
      (node (ref "U101") (pin "15") (pinfunction "VDD(3V3)_15") (pintype "power_in"))
      (node (ref "U101") (pin "165") (pinfunction "VDD(3V3)_165") (pintype "power_in"))
      (node (ref "U101") (pin "174") (pinfunction "VDD(DCDC)(3V3)_174") (pintype "power_in"))
      (node (ref "U101") (pin "181") (pinfunction "VDD(3V3)_181") (pintype "power_in"))
      (node (ref "U101") (pin "198") (pinfunction "VDD(3V3)_198") (pintype "power_in"))
      (node (ref "U101") (pin "24") (pinfunction "VREF_24") (pintype "input"))
      (node (ref "U101") (pin "26") (pinfunction "VDD(DCDC)(3V3)_26") (pintype "power_in"))
      (node (ref "U101") (pin "38") (pinfunction "VBAT_38") (pintype "power_in"))
      (node (ref "U101") (pin "60") (pinfunction "VDD(3V3)_60") (pintype "power_in"))
      (node (ref "U101") (pin "71") (pinfunction "VDD(3V3)_71") (pintype "power_in"))
      (node (ref "U101") (pin "86") (pinfunction "VDD(DCDC)(3V3)_86") (pintype "power_in"))
      (node (ref "U101") (pin "89") (pinfunction "VDD(3V3)_89") (pintype "power_in"))
      (node (ref "U101") (pin "9") (pinfunction "DBGEN_9") (pintype "input"))
      (node (ref "U102") (pin "37") (pinfunction "VCC_37") (pintype "power_in"))
      (node (ref "U102") (pin "47") (pinfunction "~{BYTE}_47") (pintype "input"))
      (node (ref "U103") (pin "11") (pinfunction "VDD1_11") (pintype "power_in"))
      (node (ref "U103") (pin "33") (pinfunction "VDD2_33") (pintype "power_in"))
    )
    (net (code "108") (name "GND") (class "Default")
      (node (ref "C101") (pin "1") (pinfunction "1_1") (pintype "passive"))
      (node (ref "C102") (pin "1") (pinfunction "1_1") (pintype "passive"))
      (node (ref "C103") (pin "1") (pinfunction "1_1") (pintype "passive"))
      (node (ref "C104") (pin "1") (pinfunction "1_1") (pintype "passive"))
      (node (ref "C105") (pin "1") (pinfunction "1_1") (pintype "passive"))
      (node (ref "C106") (pin "1") (pinfunction "1_1") (pintype "passive"))
      (node (ref "C107") (pin "1") (pinfunction "1_1") (pintype "passive"))
      (node (ref "C108") (pin "1") (pinfunction "1_1") (pintype "passive"))
      (node (ref "C109") (pin "1") (pinfunction "1_1") (pintype "passive"))
      (node (ref "C110") (pin "1") (pinfunction "1_1") (pintype "passive"))
      (node (ref "C111") (pin "1") (pinfunction "1_1") (pintype "passive"))
      (node (ref "C112") (pin "1") (pinfunction "1_1") (pintype "passive"))
      (node (ref "C113") (pin "1") (pinfunction "1_1") (pintype "passive"))
      (node (ref "C114") (pin "1") (pinfunction "1_1") (pintype "passive"))
      (node (ref "C115") (pin "1") (pinfunction "1_1") (pintype "passive"))
      (node (ref "C116") (pin "1") (pinfunction "1_1") (pintype "passive"))
      (node (ref "C117") (pin "1") (pinfunction "1_1") (pintype "passive"))
      (node (ref "C118") (pin "1") (pinfunction "1_1") (pintype "passive"))
      (node (ref "C119") (pin "1") (pinfunction "1_1") (pintype "passive"))
      (node (ref "C120") (pin "2") (pinfunction "2_2") (pintype "passive"))
      (node (ref "C121") (pin "1") (pinfunction "1_1") (pintype "passive"))
      (node (ref "C122") (pin "2") (pinfunction "2_2") (pintype "passive"))
      (node (ref "C123") (pin "1") (pinfunction "1_1") (pintype "passive"))
      (node (ref "R101") (pin "2") (pinfunction "2_2") (pintype "passive"))
      (node (ref "R104") (pin "2") (pinfunction "2_2") (pintype "passive"))
      (node (ref "U101") (pin "114") (pinfunction "VSSIO_114") (pintype "power_in"))
      (node (ref "U101") (pin "133") (pinfunction "VSSIO_133") (pintype "power_in"))
      (node (ref "U101") (pin "148") (pinfunction "VSSIO_148") (pintype "power_in"))
      (node (ref "U101") (pin "169") (pinfunction "VSSIO_169") (pintype "power_in"))
      (node (ref "U101") (pin "172") (pinfunction "VSSCORE_172") (pintype "power_in"))
      (node (ref "U101") (pin "189") (pinfunction "VSSIO_189") (pintype "power_in"))
      (node (ref "U101") (pin "200") (pinfunction "VSSIO_200") (pintype "power_in"))
      (node (ref "U101") (pin "22") (pinfunction "VSSA_22") (pintype "power_in"))
      (node (ref "U101") (pin "32") (pinfunction "VSSCORE_32") (pintype "power_in"))
      (node (ref "U101") (pin "33") (pinfunction "VSSIO_33") (pintype "power_in"))
      (node (ref "U101") (pin "63") (pinfunction "VSSIO_63") (pintype "power_in"))
      (node (ref "U101") (pin "77") (pinfunction "VSSIO_77") (pintype "power_in"))
      (node (ref "U101") (pin "84") (pinfunction "VSSCORE_84") (pintype "power_in"))
      (node (ref "U101") (pin "93") (pinfunction "VSSIO_93") (pintype "power_in"))
      (node (ref "U102") (pin "27") (pinfunction "VSS2_27") (pintype "power_in"))
      (node (ref "U102") (pin "46") (pinfunction "VSS1_46") (pintype "power_in"))
      (node (ref "U103") (pin "12") (pinfunction "VSS1_12") (pintype "power_in"))
      (node (ref "U103") (pin "34") (pinfunction "VSS2_34") (pintype "power_in"))
      (node (ref "X101") (pin "3") (pinfunction "3_3") (pintype "passive"))
    )
    (net (code "109") (name "Net-(U101F-RTCX1)") (class "Default")
      (node (ref "C122") (pin "1") (pinfunction "1_1") (pintype "passive"))
      (node (ref "U101") (pin "34") (pinfunction "RTCX1_34") (pintype "input"))
      (node (ref "X102") (pin "2") (pinfunction "OSC2_2") (pintype "passive"))
    )
    (net (code "110") (name "Net-(U101F-RTCX2)") (class "Default")
      (node (ref "C123") (pin "2") (pinfunction "2_2") (pintype "passive"))
      (node (ref "U101") (pin "36") (pinfunction "RTCX2_36") (pintype "output"))
      (node (ref "X102") (pin "1") (pinfunction "OSC1_1") (pintype "passive"))
    )
    (net (code "111") (name "Net-(U101F-XTAL1)") (class "Default")
      (node (ref "C120") (pin "1") (pinfunction "1_1") (pintype "passive"))
      (node (ref "U101") (pin "44") (pinfunction "XTAL1_44") (pintype "input"))
      (node (ref "X101") (pin "1") (pinfunction "OSC1_1") (pintype "passive"))
    )
    (net (code "112") (name "Net-(U101F-XTAL2)") (class "Default")
      (node (ref "C121") (pin "2") (pinfunction "2_2") (pintype "passive"))
      (node (ref "U101") (pin "46") (pinfunction "XTAL2_46") (pintype "output"))
      (node (ref "X101") (pin "2") (pinfunction "OSC2_2") (pintype "passive"))
    )
    (net (code "113") (name "Net-(U101F-~{RSTOUT})") (class "Default")
      (node (ref "R101") (pin "1") (pinfunction "1_1") (pintype "passive"))
      (node (ref "U101") (pin "29") (pinfunction "~{RSTOUT}_29") (pintype "output"))
    )
    (net (code "114") (name "Net-(U101H-VDDA)") (class "Default")
      (node (ref "C114") (pin "2") (pinfunction "2_2") (pintype "passive"))
      (node (ref "C115") (pin "2") (pinfunction "2_2") (pintype "passive"))
      (node (ref "FB101") (pin "2") (pinfunction "2_2") (pintype "passive"))
      (node (ref "U101") (pin "20") (pinfunction "VDDA_20") (pintype "power_in"))
    )
    (net (code "115") (name "unconnected-(U101A-P0[0]{slash}RD1{slash}TXD3{slash}SDA1-Pad94)") (class "Default")
      (node (ref "U101") (pin "94") (pinfunction "P0[0]/RD1/TXD3/SDA1_94") (pintype "bidirectional"))
    )
    (net (code "116") (name "unconnected-(U101A-P0[1]{slash}TD1{slash}RXD3{slash}SCL1-Pad96)") (class "Default")
      (node (ref "U101") (pin "96") (pinfunction "P0[1]/TD1/RXD3/SCL1_96") (pintype "bidirectional"))
    )
    (net (code "117") (name "unconnected-(U101A-P0[4]{slash}I2SRX_CLK{slash}RD2{slash}CAP2[0]-Pad168)") (class "Default")
      (node (ref "U101") (pin "168") (pinfunction "P0[4]/I2SRX_CLK/RD2/CAP2[0]_168") (pintype "bidirectional"))
    )
    (net (code "118") (name "unconnected-(U101A-P0[5]{slash}I2SRX_WS{slash}TD2{slash}CAP2[1]-Pad166)") (class "Default")
      (node (ref "U101") (pin "166") (pinfunction "P0[5]/I2SRX_WS/TD2/CAP2[1]_166") (pintype "bidirectional"))
    )
    (net (code "119") (name "unconnected-(U101A-P0[6]{slash}I2SRX_SDA{slash}SSEL1{slash}MAT2[0]-Pad164)") (class "Default")
      (node (ref "U101") (pin "164") (pinfunction "P0[6]/I2SRX_SDA/SSEL1/MAT2[0]_164") (pintype "bidirectional"))
    )
    (net (code "120") (name "unconnected-(U101A-P0[7]{slash}I2STX_CLK{slash}SCK1{slash}MAT2[1]-Pad162)") (class "Default")
      (node (ref "U101") (pin "162") (pinfunction "P0[7]/I2STX_CLK/SCK1/MAT2[1]_162") (pintype "bidirectional"))
    )
    (net (code "121") (name "unconnected-(U101A-P0[8]{slash}I2STX_WS{slash}MISO1{slash}MAT2[2]-Pad160)") (class "Default")
      (node (ref "U101") (pin "160") (pinfunction "P0[8]/I2STX_WS/MISO1/MAT2[2]_160") (pintype "bidirectional"))
    )
    (net (code "122") (name "unconnected-(U101A-P0[9]{slash}I2STX_SDA{slash}MOSI1{slash}MAT2[3]-Pad158)") (class "Default")
      (node (ref "U101") (pin "158") (pinfunction "P0[9]/I2STX_SDA/MOSI1/MAT2[3]_158") (pintype "bidirectional"))
    )
    (net (code "123") (name "unconnected-(U101A-P0[10]{slash}TXD2{slash}SDA2{slash}MAT3[0]-Pad98)") (class "Default")
      (node (ref "U101") (pin "98") (pinfunction "P0[10]/TXD2/SDA2/MAT3[0]_98") (pintype "bidirectional"))
    )
    (net (code "124") (name "unconnected-(U101A-P0[11]{slash}RXD2{slash}SCL2{slash}MAT3[1]-Pad100)") (class "Default")
      (node (ref "U101") (pin "100") (pinfunction "P0[11]/RXD2/SCL2/MAT3[1]_100") (pintype "bidirectional"))
    )
    (net (code "125") (name "unconnected-(U101A-P0[12]{slash}~{USB_PPWR}2{slash}MISO1{slash}AD0[6]-Pad41)") (class "Default")
      (node (ref "U101") (pin "41") (pinfunction "P0[12]/~{USB_PPWR}2/MISO1/AD0[6]_41") (pintype "bidirectional"))
    )
    (net (code "126") (name "unconnected-(U101A-P0[13]{slash}USB_UP_LED2{slash}MOSI1{slash}AD0[7]-Pad45)") (class "Default")
      (node (ref "U101") (pin "45") (pinfunction "P0[13]/USB_UP_LED2/MOSI1/AD0[7]_45") (pintype "bidirectional"))
    )
    (net (code "127") (name "unconnected-(U101A-P0[15]{slash}TXD1{slash}SCK0{slash}SCK-Pad128)") (class "Default")
      (node (ref "U101") (pin "128") (pinfunction "P0[15]/TXD1/SCK0/SCK_128") (pintype "bidirectional"))
    )
    (net (code "128") (name "unconnected-(U101A-P0[16]{slash}RXD1{slash}SSEL0{slash}SSEL-Pad130)") (class "Default")
      (node (ref "U101") (pin "130") (pinfunction "P0[16]/RXD1/SSEL0/SSEL_130") (pintype "bidirectional"))
    )
    (net (code "129") (name "unconnected-(U101A-P0[17]{slash}CTS1{slash}MISO0{slash}MISO-Pad126)") (class "Default")
      (node (ref "U101") (pin "126") (pinfunction "P0[17]/CTS1/MISO0/MISO_126") (pintype "bidirectional"))
    )
    (net (code "130") (name "unconnected-(U101A-P0[18]{slash}DCD1{slash}MOSI0{slash}MOSI-Pad124)") (class "Default")
      (node (ref "U101") (pin "124") (pinfunction "P0[18]/DCD1/MOSI0/MOSI_124") (pintype "bidirectional"))
    )
    (net (code "131") (name "unconnected-(U101A-P0[19]{slash}DSR1{slash}MCICLK{slash}SDA1-Pad122)") (class "Default")
      (node (ref "U101") (pin "122") (pinfunction "P0[19]/DSR1/MCICLK/SDA1_122") (pintype "bidirectional"))
    )
    (net (code "132") (name "unconnected-(U101A-P0[20]{slash}DTR1{slash}MCICMD{slash}SCL1-Pad120)") (class "Default")
      (node (ref "U101") (pin "120") (pinfunction "P0[20]/DTR1/MCICMD/SCL1_120") (pintype "bidirectional"))
    )
    (net (code "133") (name "unconnected-(U101A-P0[21]{slash}RI1{slash}MCIPWR{slash}RD1-Pad118)") (class "Default")
      (node (ref "U101") (pin "118") (pinfunction "P0[21]/RI1/MCIPWR/RD1_118") (pintype "bidirectional"))
    )
    (net (code "134") (name "unconnected-(U101A-P0[22]{slash}RTS1{slash}MCIDAT0{slash}TD1-Pad116)") (class "Default")
      (node (ref "U101") (pin "116") (pinfunction "P0[22]/RTS1/MCIDAT0/TD1_116") (pintype "bidirectional"))
    )
    (net (code "135") (name "unconnected-(U101A-P0[23]{slash}AD0[0]{slash}I2SRX_CLK{slash}CAP3[0]-Pad18)") (class "Default")
      (node (ref "U101") (pin "18") (pinfunction "P0[23]/AD0[0]/I2SRX_CLK/CAP3[0]_18") (pintype "bidirectional"))
    )
    (net (code "136") (name "unconnected-(U101A-P0[24]{slash}AD0[1]{slash}I2SRX_WS{slash}CAP3[1]-Pad16)") (class "Default")
      (node (ref "U101") (pin "16") (pinfunction "P0[24]/AD0[1]/I2SRX_WS/CAP3[1]_16") (pintype "bidirectional"))
    )
    (net (code "137") (name "unconnected-(U101A-P0[25]{slash}AD0[2]{slash}I2SRX_SDA{slash}TXD3-Pad14)") (class "Default")
      (node (ref "U101") (pin "14") (pinfunction "P0[25]/AD0[2]/I2SRX_SDA/TXD3_14") (pintype "bidirectional"))
    )
    (net (code "138") (name "unconnected-(U101A-P0[26]{slash}AD0[3]{slash}AOUT{slash}RXD3-Pad12)") (class "Default")
      (node (ref "U101") (pin "12") (pinfunction "P0[26]/AD0[3]/AOUT/RXD3_12") (pintype "bidirectional"))
    )
    (net (code "139") (name "unconnected-(U101A-P0[27]{slash}SDA0-Pad50)") (class "Default")
      (node (ref "U101") (pin "50") (pinfunction "P0[27]/SDA0_50") (pintype "bidirectional"))
    )
    (net (code "140") (name "unconnected-(U101A-P0[28]{slash}SCL0-Pad48)") (class "Default")
      (node (ref "U101") (pin "48") (pinfunction "P0[28]/SCL0_48") (pintype "bidirectional"))
    )
    (net (code "141") (name "unconnected-(U101A-P0[29]{slash}USB_D+1-Pad61)") (class "Default")
      (node (ref "U101") (pin "61") (pinfunction "P0[29]/USB_D+1_61") (pintype "bidirectional"))
    )
    (net (code "142") (name "unconnected-(U101A-P0[30]{slash}USB_D-1-Pad62)") (class "Default")
      (node (ref "U101") (pin "62") (pinfunction "P0[30]/USB_D-1_62") (pintype "bidirectional"))
    )
    (net (code "143") (name "unconnected-(U101A-P0[31]{slash}USB_D+2-Pad51)") (class "Default")
      (node (ref "U101") (pin "51") (pinfunction "P0[31]/USB_D+2_51") (pintype "bidirectional"))
    )
    (net (code "144") (name "unconnected-(U101B-P1[0]{slash}ENET_TXD0-Pad196)") (class "Default")
      (node (ref "U101") (pin "196") (pinfunction "P1[0]/ENET_TXD0_196") (pintype "bidirectional"))
    )
    (net (code "145") (name "unconnected-(U101B-P1[1]{slash}ENET_TXD1-Pad194)") (class "Default")
      (node (ref "U101") (pin "194") (pinfunction "P1[1]/ENET_TXD1_194") (pintype "bidirectional"))
    )
    (net (code "146") (name "unconnected-(U101B-P1[2]{slash}ENET_TXD2{slash}MCICLK{slash}PWM0[1]-Pad185)") (class "Default")
      (node (ref "U101") (pin "185") (pinfunction "P1[2]/ENET_TXD2/MCICLK/PWM0[1]_185") (pintype "bidirectional"))
    )
    (net (code "147") (name "unconnected-(U101B-P1[3]{slash}ENET_TXD3{slash}MCICMD{slash}PWM0[2]-Pad177)") (class "Default")
      (node (ref "U101") (pin "177") (pinfunction "P1[3]/ENET_TXD3/MCICMD/PWM0[2]_177") (pintype "bidirectional"))
    )
    (net (code "148") (name "unconnected-(U101B-P1[4]{slash}ENET_TX_EN-Pad192)") (class "Default")
      (node (ref "U101") (pin "192") (pinfunction "P1[4]/ENET_TX_EN_192") (pintype "bidirectional"))
    )
    (net (code "149") (name "unconnected-(U101B-P1[5]{slash}ENET_TX_ER{slash}MCIPWR{slash}PWM0[3]-Pad156)") (class "Default")
      (node (ref "U101") (pin "156") (pinfunction "P1[5]/ENET_TX_ER/MCIPWR/PWM0[3]_156") (pintype "bidirectional"))
    )
    (net (code "150") (name "unconnected-(U101B-P1[6]{slash}ENET_TX_CLK{slash}MCIDAT0{slash}PWM0[4]-Pad171)") (class "Default")
      (node (ref "U101") (pin "171") (pinfunction "P1[6]/ENET_TX_CLK/MCIDAT0/PWM0[4]_171") (pintype "bidirectional"))
    )
    (net (code "151") (name "unconnected-(U101B-P1[7]{slash}ENET_COL{slash}MCIDAT1{slash}PWM0[5]-Pad153)") (class "Default")
      (node (ref "U101") (pin "153") (pinfunction "P1[7]/ENET_COL/MCIDAT1/PWM0[5]_153") (pintype "bidirectional"))
    )
    (net (code "152") (name "unconnected-(U101B-P1[8]{slash}ENET_CRS_DV{slash}ENET_CRS-Pad190)") (class "Default")
      (node (ref "U101") (pin "190") (pinfunction "P1[8]/ENET_CRS_DV/ENET_CRS_190") (pintype "bidirectional"))
    )
    (net (code "153") (name "unconnected-(U101B-P1[9]{slash}ENET_RXD0-Pad188)") (class "Default")
      (node (ref "U101") (pin "188") (pinfunction "P1[9]/ENET_RXD0_188") (pintype "bidirectional"))
    )
    (net (code "154") (name "unconnected-(U101B-P1[10]{slash}ENET_RXD1-Pad186)") (class "Default")
      (node (ref "U101") (pin "186") (pinfunction "P1[10]/ENET_RXD1_186") (pintype "bidirectional"))
    )
    (net (code "155") (name "unconnected-(U101B-P1[11]{slash}ENET_RXD2{slash}MCIDAT2{slash}PWM0[6]-Pad163)") (class "Default")
      (node (ref "U101") (pin "163") (pinfunction "P1[11]/ENET_RXD2/MCIDAT2/PWM0[6]_163") (pintype "bidirectional"))
    )
    (net (code "156") (name "unconnected-(U101B-P1[12]{slash}ENET_RXD3{slash}MCIDAT3{slash}PCAP0[0]-Pad157)") (class "Default")
      (node (ref "U101") (pin "157") (pinfunction "P1[12]/ENET_RXD3/MCIDAT3/PCAP0[0]_157") (pintype "bidirectional"))
    )
    (net (code "157") (name "unconnected-(U101B-P1[13]{slash}ENET_RX_DV-Pad147)") (class "Default")
      (node (ref "U101") (pin "147") (pinfunction "P1[13]/ENET_RX_DV_147") (pintype "bidirectional"))
    )
    (net (code "158") (name "unconnected-(U101B-P1[14]{slash}ENET_RX_ER-Pad184)") (class "Default")
      (node (ref "U101") (pin "184") (pinfunction "P1[14]/ENET_RX_ER_184") (pintype "bidirectional"))
    )
    (net (code "159") (name "unconnected-(U101B-P1[15]{slash}ENET_REF_CLK{slash}ENET_RX_CLK-Pad182)") (class "Default")
      (node (ref "U101") (pin "182") (pinfunction "P1[15]/ENET_REF_CLK/ENET_RX_CLK_182") (pintype "bidirectional"))
    )
    (net (code "160") (name "unconnected-(U101B-P1[16]{slash}ENET_MDC-Pad180)") (class "Default")
      (node (ref "U101") (pin "180") (pinfunction "P1[16]/ENET_MDC_180") (pintype "bidirectional"))
    )
    (net (code "161") (name "unconnected-(U101B-P1[17]{slash}ENET_MDIO-Pad178)") (class "Default")
      (node (ref "U101") (pin "178") (pinfunction "P1[17]/ENET_MDIO_178") (pintype "bidirectional"))
    )
    (net (code "162") (name "unconnected-(U101B-P1[27]{slash}~{USB_INT}1{slash}~{USB_OVRCR}1{slash}CAP0[1]-Pad88)") (class "Default")
      (node (ref "U101") (pin "88") (pinfunction "P1[27]/~{USB_INT}1/~{USB_OVRCR}1/CAP0[1]_88") (pintype "bidirectional"))
    )
    (net (code "163") (name "unconnected-(U101B-P1[28]{slash}USB_SCL1{slash}PCAP1[0]{slash}MAT0[0]-Pad90)") (class "Default")
      (node (ref "U101") (pin "90") (pinfunction "P1[28]/USB_SCL1/PCAP1[0]/MAT0[0]_90") (pintype "bidirectional"))
    )
    (net (code "164") (name "unconnected-(U101B-P1[29]{slash}USB_SDA1{slash}PCAP1[1]{slash}MAT0[1]-Pad92)") (class "Default")
      (node (ref "U101") (pin "92") (pinfunction "P1[29]/USB_SDA1/PCAP1[1]/MAT0[1]_92") (pintype "bidirectional"))
    )
    (net (code "165") (name "unconnected-(U101B-P1[30]{slash}USB_PWRD2{slash}VBUS{slash}AD0[4]-Pad42)") (class "Default")
      (node (ref "U101") (pin "42") (pinfunction "P1[30]/USB_PWRD2/VBUS/AD0[4]_42") (pintype "bidirectional"))
    )
    (net (code "166") (name "unconnected-(U101B-P1[31]{slash}~{USB_OVRCR}2{slash}SCK1{slash}AD0[5]-Pad40)") (class "Default")
      (node (ref "U101") (pin "40") (pinfunction "P1[31]/~{USB_OVRCR}2/SCK1/AD0[5]_40") (pintype "bidirectional"))
    )
    (net (code "167") (name "unconnected-(U101C-P2[0]{slash}PWM1[1]{slash}TXD1{slash}TRACECLK-Pad154)") (class "Default")
      (node (ref "U101") (pin "154") (pinfunction "P2[0]/PWM1[1]/TXD1/TRACECLK_154") (pintype "bidirectional"))
    )
    (net (code "168") (name "unconnected-(U101C-P2[5]{slash}PWM1[6]{slash}DTR1{slash}TRACEPKT0-Pad140)") (class "Default")
      (node (ref "U101") (pin "140") (pinfunction "P2[5]/PWM1[6]/DTR1/TRACEPKT0_140") (pintype "bidirectional"))
    )
    (net (code "169") (name "unconnected-(U101C-P2[14]{slash}~{CS}2{slash}CAP2[0]{slash}SDA1-Pad91)") (class "Default")
      (node (ref "U101") (pin "91") (pinfunction "P2[14]/~{CS}2/CAP2[0]/SDA1_91") (pintype "bidirectional"))
    )
    (net (code "170") (name "unconnected-(U101C-P2[16]{slash}~{CAS}-Pad87)") (class "Default")
      (node (ref "U101") (pin "87") (pinfunction "P2[16]/~{CAS}_87") (pintype "bidirectional"))
    )
    (net (code "171") (name "unconnected-(U101C-P2[22]{slash}~{DYCS}2{slash}CAP3[0]{slash}SCK0-Pad85)") (class "Default")
      (node (ref "U101") (pin "85") (pinfunction "P2[22]/~{DYCS}2/CAP3[0]/SCK0_85") (pintype "bidirectional"))
    )
    (net (code "172") (name "unconnected-(U101C-P2[24]{slash}CKEOUT0-Pad53)") (class "Default")
      (node (ref "U101") (pin "53") (pinfunction "P2[24]/CKEOUT0_53") (pintype "bidirectional"))
    )
    (net (code "173") (name "unconnected-(U101C-P2[27]{slash}CKEOUT3{slash}MAT3[1]{slash}MOSI0-Pad47)") (class "Default")
      (node (ref "U101") (pin "47") (pinfunction "P2[27]/CKEOUT3/MAT3[1]/MOSI0_47") (pintype "bidirectional"))
    )
    (net (code "174") (name "unconnected-(U101C-P2[28]{slash}DQMOUT0-Pad49)") (class "Default")
      (node (ref "U101") (pin "49") (pinfunction "P2[28]/DQMOUT0_49") (pintype "bidirectional"))
    )
    (net (code "175") (name "unconnected-(U101C-P2[29]{slash}DQMOUT1-Pad43)") (class "Default")
      (node (ref "U101") (pin "43") (pinfunction "P2[29]/DQMOUT1_43") (pintype "bidirectional"))
    )
    (net (code "176") (name "unconnected-(U101C-P2[30]{slash}DQMOUT2{slash}MAT3[2]{slash}SDA2-Pad31)") (class "Default")
      (node (ref "U101") (pin "31") (pinfunction "P2[30]/DQMOUT2/MAT3[2]/SDA2_31") (pintype "bidirectional"))
    )
    (net (code "177") (name "unconnected-(U101C-P2[31]{slash}DQMOUT3{slash}MAT3[3]{slash}SCL2-Pad39)") (class "Default")
      (node (ref "U101") (pin "39") (pinfunction "P2[31]/DQMOUT3/MAT3[3]/SCL2_39") (pintype "bidirectional"))
    )
    (net (code "178") (name "unconnected-(U101D-P3[16]{slash}D16{slash}PWM0[1]{slash}TXD1-Pad137)") (class "Default")
      (node (ref "U101") (pin "137") (pinfunction "P3[16]/D16/PWM0[1]/TXD1_137") (pintype "bidirectional"))
    )
    (net (code "179") (name "unconnected-(U101D-P3[17]{slash}D17{slash}PWM0[2]{slash}RXD1-Pad143)") (class "Default")
      (node (ref "U101") (pin "143") (pinfunction "P3[17]/D17/PWM0[2]/RXD1_143") (pintype "bidirectional"))
    )
    (net (code "180") (name "unconnected-(U101D-P3[18]{slash}D18{slash}PWM0[3]{slash}CTS1-Pad151)") (class "Default")
      (node (ref "U101") (pin "151") (pinfunction "P3[18]/D18/PWM0[3]/CTS1_151") (pintype "bidirectional"))
    )
    (net (code "181") (name "unconnected-(U101D-P3[19]{slash}D19{slash}PWM0[4]{slash}DCD1-Pad161)") (class "Default")
      (node (ref "U101") (pin "161") (pinfunction "P3[19]/D19/PWM0[4]/DCD1_161") (pintype "bidirectional"))
    )
    (net (code "182") (name "unconnected-(U101D-P3[20]{slash}D20{slash}PWM0[5]{slash}DSR1-Pad167)") (class "Default")
      (node (ref "U101") (pin "167") (pinfunction "P3[20]/D20/PWM0[5]/DSR1_167") (pintype "bidirectional"))
    )
    (net (code "183") (name "unconnected-(U101D-P3[21]{slash}D21{slash}PWM0[6]{slash}DTR1-Pad175)") (class "Default")
      (node (ref "U101") (pin "175") (pinfunction "P3[21]/D21/PWM0[6]/DTR1_175") (pintype "bidirectional"))
    )
    (net (code "184") (name "unconnected-(U101D-P3[22]{slash}D22{slash}PCAP0[0]{slash}RI1-Pad195)") (class "Default")
      (node (ref "U101") (pin "195") (pinfunction "P3[22]/D22/PCAP0[0]/RI1_195") (pintype "bidirectional"))
    )
    (net (code "185") (name "unconnected-(U101D-P3[27]{slash}D27{slash}CAP1[0]{slash}PWM1[4]-Pad203)") (class "Default")
      (node (ref "U101") (pin "203") (pinfunction "P3[27]/D27/CAP1[0]/PWM1[4]_203") (pintype "bidirectional"))
    )
    (net (code "186") (name "unconnected-(U101D-P3[28]{slash}D28{slash}CAP1[1]{slash}PWM1[5]-Pad5)") (class "Default")
      (node (ref "U101") (pin "5") (pinfunction "P3[28]/D28/CAP1[1]/PWM1[5]_5") (pintype "bidirectional"))
    )
    (net (code "187") (name "unconnected-(U101D-P3[29]{slash}D29{slash}MAT1[0]{slash}PWM1[6]-Pad11)") (class "Default")
      (node (ref "U101") (pin "11") (pinfunction "P3[29]/D29/MAT1[0]/PWM1[6]_11") (pintype "bidirectional"))
    )
    (net (code "188") (name "unconnected-(U101D-P3[30]{slash}D30{slash}MAT1[1]{slash}RTS1-Pad19)") (class "Default")
      (node (ref "U101") (pin "19") (pinfunction "P3[30]/D30/MAT1[1]/RTS1_19") (pintype "bidirectional"))
    )
    (net (code "189") (name "unconnected-(U101D-P3[31]{slash}D31{slash}MAT1[2]-Pad25)") (class "Default")
      (node (ref "U101") (pin "25") (pinfunction "P3[31]/D31/MAT1[2]_25") (pintype "bidirectional"))
    )
    (net (code "190") (name "unconnected-(U101E-P4[0]{slash}A0-Pad75)") (class "Default")
      (node (ref "U101") (pin "75") (pinfunction "P4[0]/A0_75") (pintype "bidirectional+no_connect"))
    )
    (net (code "191") (name "unconnected-(U101E-P4[28]{slash}BLS2{slash}MAT2[0]{slash}TXD3-Pad170)") (class "Default")
      (node (ref "U101") (pin "170") (pinfunction "P4[28]/BLS2/MAT2[0]/TXD3_170") (pintype "bidirectional"))
    )
    (net (code "192") (name "unconnected-(U101E-P4[29]{slash}BLS3{slash}MAT2[1]{slash}RXD3-Pad176)") (class "Default")
      (node (ref "U101") (pin "176") (pinfunction "P4[29]/BLS3/MAT2[1]/RXD3_176") (pintype "bidirectional"))
    )
    (net (code "193") (name "unconnected-(U101F-ALARM-Pad37)") (class "Default")
      (node (ref "U101") (pin "37") (pinfunction "ALARM_37") (pintype "output+no_connect"))
    )
    (net (code "194") (name "unconnected-(U101F-USB_D-2-Pad52)") (class "Default")
      (node (ref "U101") (pin "52") (pinfunction "USB_D-2_52") (pintype "bidirectional+no_connect"))
    )
    (net (code "195") (name "unconnected-(U101I-NC-Pad30)") (class "Default")
      (node (ref "U101") (pin "30") (pinfunction "NC_30") (pintype "passive+no_connect"))
    )
    (net (code "196") (name "unconnected-(U101I-NC-Pad117)") (class "Default")
      (node (ref "U101") (pin "117") (pinfunction "NC_117") (pintype "passive+no_connect"))
    )
    (net (code "197") (name "unconnected-(U101I-NC-Pad141)") (class "Default")
      (node (ref "U101") (pin "141") (pinfunction "NC_141") (pintype "passive+no_connect"))
    )
    (net (code "198") (name "unconnected-(U102-DNU-Pad13)") (class "Default")
      (node (ref "U102") (pin "13") (pinfunction "DNU_13") (pintype "passive+no_connect"))
    )
    (net (code "199") (name "unconnected-(U102-NC-Pad10)") (class "Default")
      (node (ref "U102") (pin "10") (pinfunction "NC_10") (pintype "passive+no_connect"))
    )
  )
)
